# mcu_power.net
KiCad netlist of a schematic drawn in Altium Designer
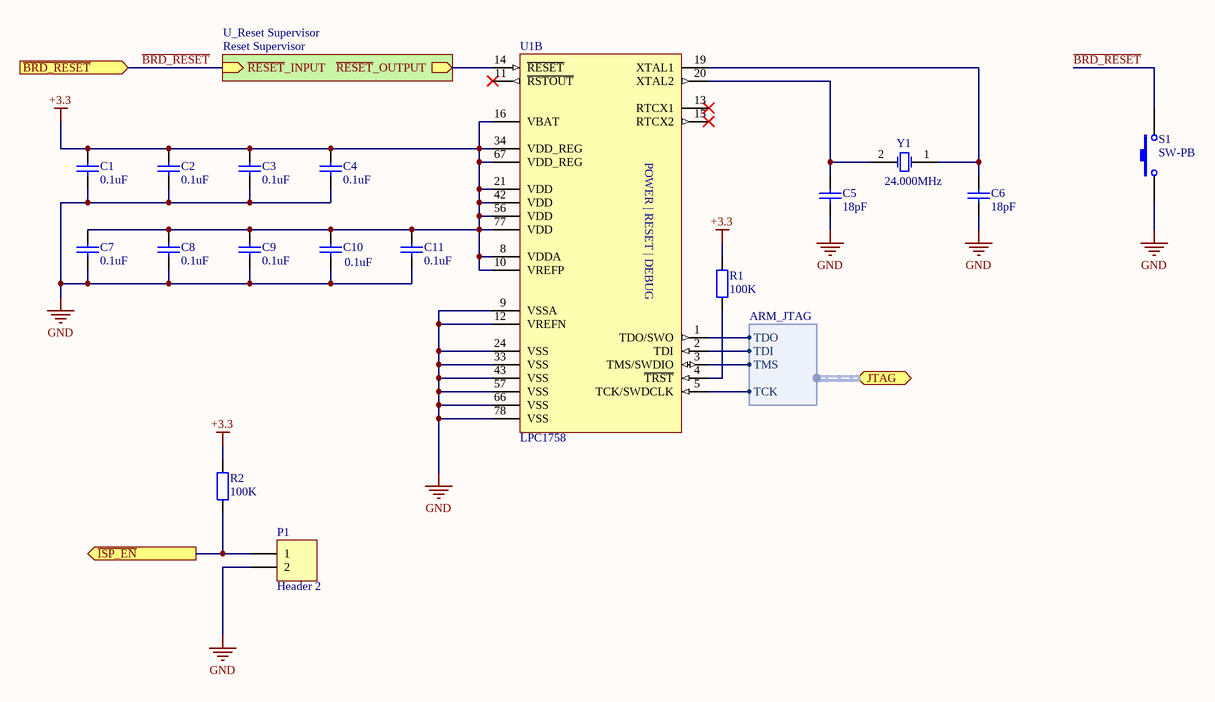
[diagram p0: mcu_power.SchDoc]

(export (version "E")
  (design (tool "Eeschema 10.0.6"))
  (components
    (comp (ref "C1")
      (value "0.1uF")
      (footprint "C0603")
      (description "Capacitor")
      (fields (field (name "Comment") "Cap"))
      (libsource (lib "Miscellaneous Devices") (part "Cap"))
    )
    (comp (ref "C2")
      (value "0.1uF")
      (footprint "C0603")
      (description "Capacitor")
      (fields (field (name "Comment") "Cap"))
      (libsource (lib "Miscellaneous Devices") (part "Cap"))
    )
    (comp (ref "C3")
      (value "0.1uF")
      (footprint "C0603")
      (description "Capacitor")
      (fields (field (name "Comment") "Cap"))
      (libsource (lib "Miscellaneous Devices") (part "Cap"))
    )
    (comp (ref "C4")
      (value "0.1uF")
      (footprint "C0603")
      (description "Capacitor")
      (fields (field (name "Comment") "Cap"))
      (libsource (lib "Miscellaneous Devices") (part "Cap"))
    )
    (comp (ref "C5")
      (value "18pF")
      (footprint "C0603")
      (description "Capacitor")
      (fields (field (name "Comment") "Cap"))
      (libsource (lib "Miscellaneous Devices") (part "Cap"))
    )
    (comp (ref "C6")
      (value "18pF")
      (footprint "C0603")
      (description "Capacitor")
      (fields (field (name "Comment") "Cap"))
      (libsource (lib "Miscellaneous Devices") (part "Cap"))
    )
    (comp (ref "C7")
      (value "0.1uF")
      (footprint "C0603")
      (description "Capacitor")
      (fields (field (name "Comment") "Cap"))
      (libsource (lib "Miscellaneous Devices") (part "Cap"))
    )
    (comp (ref "C8")
      (value "0.1uF")
      (footprint "C0603")
      (description "Capacitor")
      (fields (field (name "Comment") "Cap"))
      (libsource (lib "Miscellaneous Devices") (part "Cap"))
    )
    (comp (ref "C9")
      (value "0.1uF")
      (footprint "C0603")
      (description "Capacitor")
      (fields (field (name "Comment") "Cap"))
      (libsource (lib "Miscellaneous Devices") (part "Cap"))
    )
    (comp (ref "C10")
      (value "0.1uF")
      (footprint "C0603")
      (description "Capacitor")
      (fields (field (name "Comment") "Cap"))
      (libsource (lib "Miscellaneous Devices") (part "Cap"))
    )
    (comp (ref "C11")
      (value "0.1uF")
      (footprint "C0603")
      (description "Capacitor")
      (fields (field (name "Comment") "Cap"))
      (libsource (lib "Miscellaneous Devices") (part "Cap"))
    )
    (comp (ref "P1")
      (value "Header 2")
      (footprint "HDR1X2")
      (description "Header, 2-Pin")
      (fields (field (name "PUBLISHER") "Altium Limited"))
      (libsource (lib "Miscellaneous Connectors") (part "Header 2"))
    )
    (comp (ref "R1")
      (value "100K")
      (footprint "R0603")
      (description "Resistor")
      (fields (field (name "Comment") "Res"))
      (libsource (lib "Miscellaneous Devices") (part "Res2"))
    )
    (comp (ref "R2")
      (value "100K")
      (footprint "R0603")
      (description "Resistor")
      (fields (field (name "Comment") "Res"))
      (libsource (lib "Miscellaneous Devices") (part "Res2"))
    )
    (comp (ref "S1")
      (value "SW-PB")
      (footprint "DTSM-32S-B")
      (description "Switch")
      (fields (field (name "PUBLISHER") "Altium Limited"))
      (libsource (lib "Miscellaneous Devices") (part "SW-PB"))
    )
    (comp (ref "U1")
      (value "LPC1758")
      (footprint "LPC1758FBD80")
      (description "NXP - LPC1758FBD80 - MCU, 32BIT, ARM CORTEX M3, 80LQFP")
      (libsource (lib "LPC1758") (part "LPC1758"))
    )
    (comp (ref "Y1")
      (value "24.000MHz")
      (footprint "C3E-24.000-12-3030-X")
      (description "Crystal Oscillator")
      (fields (field (name "Comment") "XTAL"))
      (libsource (lib "Miscellaneous Devices") (part "XTAL"))
    )
  )
  (nets
    (net (code "2") (name "+3.3") (class "Default")
      (node (ref "C1") (pin "1") (pinfunction "1_1") (pintype "passive"))
      (node (ref "C10") (pin "1") (pinfunction "1_1") (pintype "passive"))
      (node (ref "C11") (pin "1") (pinfunction "1_1") (pintype "passive"))
      (node (ref "C2") (pin "1") (pinfunction "1_1") (pintype "passive"))
      (node (ref "C3") (pin "1") (pinfunction "1_1") (pintype "passive"))
      (node (ref "C4") (pin "1") (pinfunction "1_1") (pintype "passive"))
      (node (ref "C7") (pin "1") (pinfunction "1_1") (pintype "passive"))
      (node (ref "C8") (pin "1") (pinfunction "1_1") (pintype "passive"))
      (node (ref "C9") (pin "1") (pinfunction "1_1") (pintype "passive"))
      (node (ref "R1") (pin "2") (pinfunction "2_2") (pintype "passive"))
      (node (ref "R2") (pin "2") (pinfunction "2_2") (pintype "passive"))
      (node (ref "U1") (pin "10") (pinfunction "VREFP_10") (pintype "passive"))
      (node (ref "U1") (pin "16") (pinfunction "VBAT_16") (pintype "power_in"))
      (node (ref "U1") (pin "21") (pinfunction "VDD_21") (pintype "power_in"))
      (node (ref "U1") (pin "34") (pinfunction "VDD_REG_34") (pintype "power_in"))
      (node (ref "U1") (pin "42") (pinfunction "VDD_42") (pintype "power_in"))
      (node (ref "U1") (pin "56") (pinfunction "VDD_56") (pintype "power_in"))
      (node (ref "U1") (pin "67") (pinfunction "VDD_REG_67") (pintype "power_in"))
      (node (ref "U1") (pin "77") (pinfunction "VDD_77") (pintype "power_in"))
      (node (ref "U1") (pin "8") (pinfunction "VDDA_8") (pintype "power_in"))
    )
    (net (code "3") (name "/TCK") (class "Default")
      (node (ref "U1") (pin "5") (pinfunction "TCK/SWDCLK_5") (pintype "input"))
    )
    (net (code "4") (name "/TDI") (class "Default")
      (node (ref "U1") (pin "2") (pinfunction "TDI_2") (pintype "input"))
    )
    (net (code "5") (name "/TDO") (class "Default")
      (node (ref "U1") (pin "1") (pinfunction "TDO/SWO_1") (pintype "output"))
    )
    (net (code "6") (name "/TMS") (class "Default")
      (node (ref "U1") (pin "3") (pinfunction "TMS/SWDIO_3") (pintype "bidirectional"))
    )
    (net (code "8") (name "/~{BRD_RESET}") (class "Default")
      (node (ref "S1") (pin "2") (pinfunction "2_2") (pintype "passive"))
    )
    (net (code "9") (name "/~{ISP_EN}") (class "Default")
      (node (ref "P1") (pin "1") (pinfunction "1_1") (pintype "passive"))
      (node (ref "R2") (pin "1") (pinfunction "1_1") (pintype "passive"))
    )
    (net (code "10") (name "/~{RESET}_OUTPUT") (class "Default")
      (node (ref "U1") (pin "14") (pinfunction "~{RESET}_14") (pintype "input"))
    )
    (net (code "11") (name "GND") (class "Default")
      (node (ref "C1") (pin "2") (pinfunction "2_2") (pintype "passive"))
      (node (ref "C10") (pin "2") (pinfunction "2_2") (pintype "passive"))
      (node (ref "C11") (pin "2") (pinfunction "2_2") (pintype "passive"))
      (node (ref "C2") (pin "2") (pinfunction "2_2") (pintype "passive"))
      (node (ref "C3") (pin "2") (pinfunction "2_2") (pintype "passive"))
      (node (ref "C4") (pin "2") (pinfunction "2_2") (pintype "passive"))
      (node (ref "C5") (pin "2") (pinfunction "2_2") (pintype "passive"))
      (node (ref "C6") (pin "2") (pinfunction "2_2") (pintype "passive"))
      (node (ref "C7") (pin "2") (pinfunction "2_2") (pintype "passive"))
      (node (ref "C8") (pin "2") (pinfunction "2_2") (pintype "passive"))
      (node (ref "C9") (pin "2") (pinfunction "2_2") (pintype "passive"))
      (node (ref "P1") (pin "2") (pinfunction "2_2") (pintype "passive"))
      (node (ref "S1") (pin "1") (pinfunction "1_1") (pintype "passive"))
      (node (ref "U1") (pin "12") (pinfunction "VREFN_12") (pintype "passive"))
      (node (ref "U1") (pin "24") (pinfunction "VSS_24") (pintype "power_in"))
      (node (ref "U1") (pin "33") (pinfunction "VSS_33") (pintype "power_in"))
      (node (ref "U1") (pin "43") (pinfunction "VSS_43") (pintype "power_in"))
      (node (ref "U1") (pin "57") (pinfunction "VSS_57") (pintype "power_in"))
      (node (ref "U1") (pin "66") (pinfunction "VSS_66") (pintype "power_in"))
      (node (ref "U1") (pin "78") (pinfunction "VSS_78") (pintype "power_in"))
      (node (ref "U1") (pin "9") (pinfunction "VSSA_9") (pintype "power_in"))
    )
    (net (code "12") (name "Net-(U1B-XTAL1)") (class "Default")
      (node (ref "C6") (pin "1") (pinfunction "1_1") (pintype "passive"))
      (node (ref "U1") (pin "19") (pinfunction "XTAL1_19") (pintype "passive"))
      (node (ref "Y1") (pin "1") (pinfunction "OSC1_1") (pintype "passive"))
    )
    (net (code "13") (name "Net-(U1B-XTAL2)") (class "Default")
      (node (ref "C5") (pin "1") (pinfunction "1_1") (pintype "passive"))
      (node (ref "U1") (pin "20") (pinfunction "XTAL2_20") (pintype "output"))
      (node (ref "Y1") (pin "2") (pinfunction "OSC2_2") (pintype "passive"))
    )
    (net (code "14") (name "Net-(U1B-~{TRST})") (class "Default")
      (node (ref "R1") (pin "1") (pinfunction "1_1") (pintype "passive"))
      (node (ref "U1") (pin "4") (pinfunction "~{TRST}_4") (pintype "input"))
    )
    (net (code "15") (name "unconnected-(U1B-RTCX1-Pad13)") (class "Default")
      (node (ref "U1") (pin "13") (pinfunction "RTCX1_13") (pintype "passive+no_connect"))
    )
    (net (code "16") (name "unconnected-(U1B-RTCX2-Pad15)") (class "Default")
      (node (ref "U1") (pin "15") (pinfunction "RTCX2_15") (pintype "output+no_connect"))
    )
    (net (code "17") (name "unconnected-(U1B-~{RSTOUT}-Pad11)") (class "Default")
      (node (ref "U1") (pin "11") (pinfunction "~{RSTOUT}_11") (pintype "output+no_connect"))
    )
  )
)
